# ssslidar_v1_0_blade_PWR_bottom.net
KiCad netlist of a schematic drawn in EAGLE
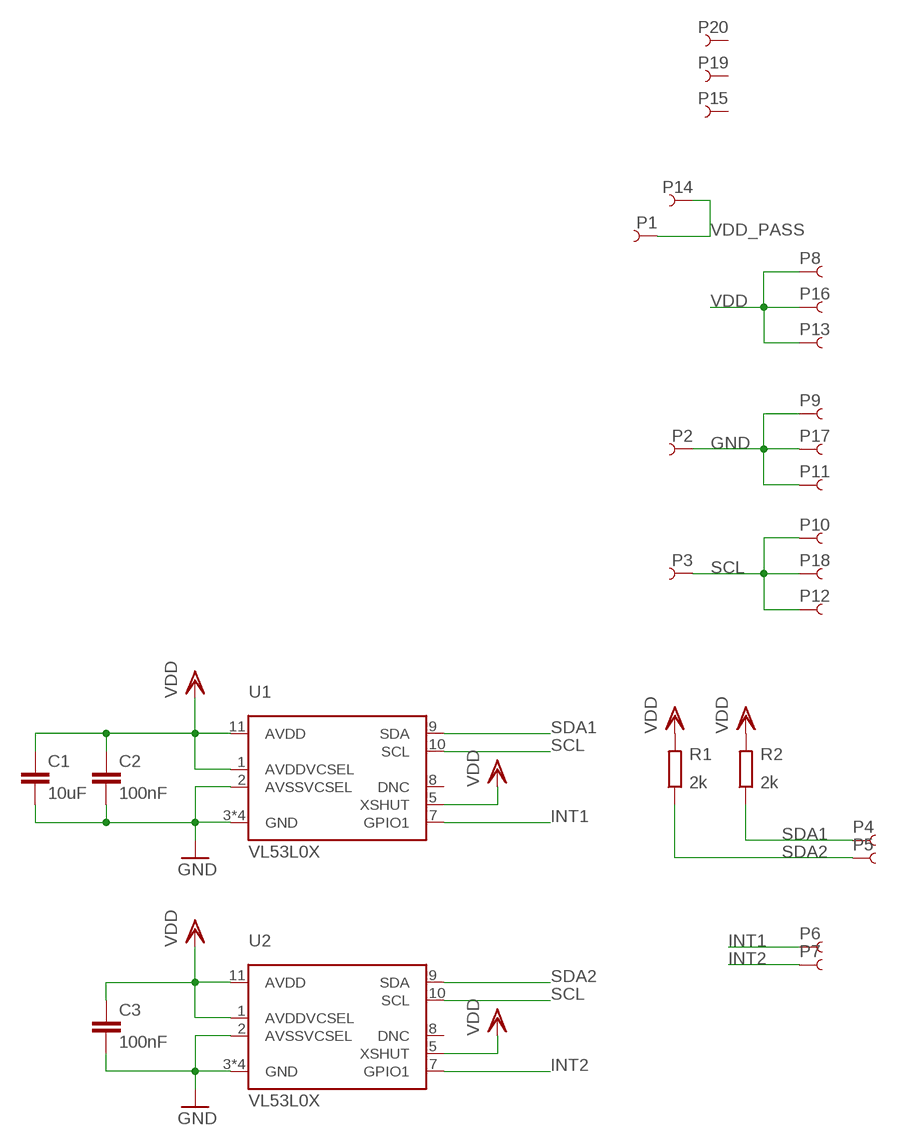
[diagram p0: schematic, sheet 1]

(export (version "E")
  (design (tool "Eeschema 10.0.6"))
  (components
    (comp (ref "C1")
      (value "10uF")
      (footprint "eagle-import:0805_N")
      (libsource (lib "eagle-import") (part "C0805"))
    )
    (comp (ref "C2")
      (value "100nF")
      (footprint "eagle-import:0402_N")
      (libsource (lib "eagle-import") (part "C0402"))
    )
    (comp (ref "C3")
      (value "100nF")
      (footprint "eagle-import:0402_N")
      (libsource (lib "eagle-import") (part "C0402"))
    )
    (comp (ref "P1")
      (value "PIN_SMD_0.8X1_RECT")
      (footprint "eagle-import:PIN_SMD_0.8X1_RECT")
      (libsource (lib "eagle-import") (part "PIN_SMD_0.8X1_RECT"))
    )
    (comp (ref "P2")
      (value "PIN_SMD_1X2")
      (footprint "eagle-import:PIN_SMD_1X2")
      (libsource (lib "eagle-import") (part "PIN_SMD_1X2"))
    )
    (comp (ref "P3")
      (value "PIN_SMD_0.8X1_RECT")
      (footprint "eagle-import:PIN_SMD_0.8X1_RECT")
      (libsource (lib "eagle-import") (part "PIN_SMD_0.8X1_RECT"))
    )
    (comp (ref "P4")
      (value "PIN_SMD_0.8X1_RECT")
      (footprint "eagle-import:PIN_SMD_0.8X1_RECT")
      (libsource (lib "eagle-import") (part "PIN_SMD_0.8X1_RECT"))
    )
    (comp (ref "P5")
      (value "PIN_SMD_0.8X1_RECT")
      (footprint "eagle-import:PIN_SMD_0.8X1_RECT")
      (libsource (lib "eagle-import") (part "PIN_SMD_0.8X1_RECT"))
    )
    (comp (ref "P6")
      (value "PIN_SMD_0.8X1_RECT")
      (footprint "eagle-import:PIN_SMD_0.8X1_RECT")
      (libsource (lib "eagle-import") (part "PIN_SMD_0.8X1_RECT"))
    )
    (comp (ref "P7")
      (value "PIN_SMD_0.8X1_RECT")
      (footprint "eagle-import:PIN_SMD_0.8X1_RECT")
      (libsource (lib "eagle-import") (part "PIN_SMD_0.8X1_RECT"))
    )
    (comp (ref "P8")
      (value "PIN_SMD_0.8X1_RECT")
      (footprint "eagle-import:PIN_SMD_0.8X1_RECT")
      (libsource (lib "eagle-import") (part "PIN_SMD_0.8X1_RECT"))
    )
    (comp (ref "P9")
      (value "PIN_SMD_1X2")
      (footprint "eagle-import:PIN_SMD_1X2")
      (libsource (lib "eagle-import") (part "PIN_SMD_1X2"))
    )
    (comp (ref "P10")
      (value "PIN_SMD_1X2")
      (footprint "eagle-import:PIN_SMD_1X2")
      (libsource (lib "eagle-import") (part "PIN_SMD_1X2"))
    )
    (comp (ref "P11")
      (value "PIN_SMD_1X2")
      (footprint "eagle-import:PIN_SMD_1X2")
      (libsource (lib "eagle-import") (part "PIN_SMD_1X2"))
    )
    (comp (ref "P12")
      (value "PIN_SMD_1X2")
      (footprint "eagle-import:PIN_SMD_1X2")
      (libsource (lib "eagle-import") (part "PIN_SMD_1X2"))
    )
    (comp (ref "P13")
      (value "PIN_SMD_1X2")
      (footprint "eagle-import:PIN_SMD_1X2")
      (libsource (lib "eagle-import") (part "PIN_SMD_1X2"))
    )
    (comp (ref "P14")
      (value "PIN_SMD_0.8X1_RECT")
      (footprint "eagle-import:PIN_SMD_0.8X1_RECT")
      (libsource (lib "eagle-import") (part "PIN_SMD_0.8X1_RECT"))
    )
    (comp (ref "P15")
      (value "PIN_SMD_0.8X1_RECT")
      (footprint "eagle-import:PIN_SMD_0.8X1_RECT")
      (libsource (lib "eagle-import") (part "PIN_SMD_0.8X1_RECT"))
    )
    (comp (ref "P16")
      (value "PIN_SMD_1X2")
      (footprint "eagle-import:PIN_SMD_1X2")
      (libsource (lib "eagle-import") (part "PIN_SMD_1X2"))
    )
    (comp (ref "P17")
      (value "PIN_SMD_1X2")
      (footprint "eagle-import:PIN_SMD_1X2")
      (libsource (lib "eagle-import") (part "PIN_SMD_1X2"))
    )
    (comp (ref "P18")
      (value "PIN_SMD_0.8X1_RECT")
      (footprint "eagle-import:PIN_SMD_0.8X1_RECT")
      (libsource (lib "eagle-import") (part "PIN_SMD_0.8X1_RECT"))
    )
    (comp (ref "P19")
      (value "PIN_SMD_0.8X1_RECT")
      (footprint "eagle-import:PIN_SMD_0.8X1_RECT")
      (libsource (lib "eagle-import") (part "PIN_SMD_0.8X1_RECT"))
    )
    (comp (ref "P20")
      (value "PIN_SMD_0.8X1_RECT")
      (footprint "eagle-import:PIN_SMD_0.8X1_RECT")
      (libsource (lib "eagle-import") (part "PIN_SMD_0.8X1_RECT"))
    )
    (comp (ref "R1")
      (value "2k")
      (footprint "eagle-import:0402_N")
      (libsource (lib "eagle-import") (part "R0402"))
    )
    (comp (ref "R2")
      (value "2k")
      (footprint "eagle-import:0402_N")
      (libsource (lib "eagle-import") (part "R0402"))
    )
    (comp (ref "U1")
      (value "VL53L0X")
      (footprint "eagle-import:VL53L0X")
      (libsource (lib "eagle-import") (part "VL53L0X"))
    )
    (comp (ref "U2")
      (value "VL53L0X")
      (footprint "eagle-import:VL53L0X")
      (libsource (lib "eagle-import") (part "VL53L0X"))
    )
  )
  (nets
    (net (code "1") (name "/INT1") (class "Default")
      (node (ref "P6") (pin "PIN") (pinfunction "1_PIN") (pintype "bidirectional"))
      (node (ref "U1") (pin "7") (pinfunction "GPIO1_7") (pintype "bidirectional"))
    )
    (net (code "2") (name "/INT2") (class "Default")
      (node (ref "P7") (pin "PIN") (pinfunction "1_PIN") (pintype "bidirectional"))
      (node (ref "U2") (pin "7") (pinfunction "GPIO1_7") (pintype "bidirectional"))
    )
    (net (code "3") (name "/SCL") (class "Default")
      (node (ref "P10") (pin "P$1") (pinfunction "1_P$1") (pintype "bidirectional"))
      (node (ref "P12") (pin "P$1") (pinfunction "1_P$1") (pintype "bidirectional"))
      (node (ref "P18") (pin "PIN") (pinfunction "1_PIN") (pintype "bidirectional"))
      (node (ref "P3") (pin "PIN") (pinfunction "1_PIN") (pintype "bidirectional"))
      (node (ref "U1") (pin "10") (pinfunction "SCL_10") (pintype "bidirectional"))
      (node (ref "U2") (pin "10") (pinfunction "SCL_10") (pintype "bidirectional"))
    )
    (net (code "4") (name "/SDA1") (class "Default")
      (node (ref "P4") (pin "PIN") (pinfunction "1_PIN") (pintype "bidirectional"))
      (node (ref "R2") (pin "1") (pinfunction "1_1") (pintype "passive"))
      (node (ref "U1") (pin "9") (pinfunction "SDA_9") (pintype "bidirectional"))
    )
    (net (code "5") (name "/SDA2") (class "Default")
      (node (ref "P5") (pin "PIN") (pinfunction "1_PIN") (pintype "bidirectional"))
      (node (ref "R1") (pin "1") (pinfunction "1_1") (pintype "passive"))
      (node (ref "U2") (pin "9") (pinfunction "SDA_9") (pintype "bidirectional"))
    )
    (net (code "6") (name "/VDD_PASS") (class "Default")
      (node (ref "P1") (pin "PIN") (pinfunction "1_PIN") (pintype "bidirectional"))
      (node (ref "P14") (pin "PIN") (pinfunction "1_PIN") (pintype "bidirectional"))
    )
    (net (code "7") (name "GND") (class "Default")
      (node (ref "C1") (pin "2") (pinfunction "2_2") (pintype "passive"))
      (node (ref "C2") (pin "2") (pinfunction "2_2") (pintype "passive"))
      (node (ref "C3") (pin "2") (pinfunction "2_2") (pintype "passive"))
      (node (ref "P11") (pin "P$1") (pinfunction "1_P$1") (pintype "bidirectional"))
      (node (ref "P17") (pin "P$1") (pinfunction "1_P$1") (pintype "bidirectional"))
      (node (ref "P2") (pin "P$1") (pinfunction "1_P$1") (pintype "bidirectional"))
      (node (ref "P9") (pin "P$1") (pinfunction "1_P$1") (pintype "bidirectional"))
      (node (ref "U1") (pin "12") (pinfunction "GND_12") (pintype "bidirectional"))
      (node (ref "U1") (pin "2") (pinfunction "AVSSVCSEL_2") (pintype "bidirectional"))
      (node (ref "U1") (pin "3") (pinfunction "GND_3") (pintype "bidirectional"))
      (node (ref "U1") (pin "4") (pinfunction "GND_4") (pintype "bidirectional"))
      (node (ref "U1") (pin "6") (pinfunction "GND_6") (pintype "bidirectional"))
      (node (ref "U2") (pin "12") (pinfunction "GND_12") (pintype "bidirectional"))
      (node (ref "U2") (pin "2") (pinfunction "AVSSVCSEL_2") (pintype "bidirectional"))
      (node (ref "U2") (pin "3") (pinfunction "GND_3") (pintype "bidirectional"))
      (node (ref "U2") (pin "4") (pinfunction "GND_4") (pintype "bidirectional"))
      (node (ref "U2") (pin "6") (pinfunction "GND_6") (pintype "bidirectional"))
    )
    (net (code "8") (name "VDD") (class "Default")
      (node (ref "C1") (pin "1") (pinfunction "1_1") (pintype "passive"))
      (node (ref "C2") (pin "1") (pinfunction "1_1") (pintype "passive"))
      (node (ref "C3") (pin "1") (pinfunction "1_1") (pintype "passive"))
      (node (ref "P13") (pin "P$1") (pinfunction "1_P$1") (pintype "bidirectional"))
      (node (ref "P16") (pin "P$1") (pinfunction "1_P$1") (pintype "bidirectional"))
      (node (ref "P8") (pin "PIN") (pinfunction "1_PIN") (pintype "bidirectional"))
      (node (ref "R1") (pin "2") (pinfunction "2_2") (pintype "passive"))
      (node (ref "R2") (pin "2") (pinfunction "2_2") (pintype "passive"))
      (node (ref "U1") (pin "1") (pinfunction "AVDDVCSEL_1") (pintype "bidirectional"))
      (node (ref "U1") (pin "11") (pinfunction "AVDD_11") (pintype "bidirectional"))
      (node (ref "U1") (pin "5") (pinfunction "XSHUT_5") (pintype "bidirectional"))
      (node (ref "U2") (pin "1") (pinfunction "AVDDVCSEL_1") (pintype "bidirectional"))
      (node (ref "U2") (pin "11") (pinfunction "AVDD_11") (pintype "bidirectional"))
      (node (ref "U2") (pin "5") (pinfunction "XSHUT_5") (pintype "bidirectional"))
    )
    (net (code "9") (name "unconnected-(P15-1-PadPIN)") (class "Default")
      (node (ref "P15") (pin "PIN") (pinfunction "1_PIN") (pintype "bidirectional"))
    )
    (net (code "10") (name "unconnected-(P19-1-PadPIN)") (class "Default")
      (node (ref "P19") (pin "PIN") (pinfunction "1_PIN") (pintype "bidirectional"))
    )
    (net (code "11") (name "unconnected-(P20-1-PadPIN)") (class "Default")
      (node (ref "P20") (pin "PIN") (pinfunction "1_PIN") (pintype "bidirectional"))
    )
    (net (code "12") (name "unconnected-(U1-DNC-Pad8)") (class "Default")
      (node (ref "U1") (pin "8") (pinfunction "DNC_8") (pintype "bidirectional"))
    )
    (net (code "13") (name "unconnected-(U2-DNC-Pad8)") (class "Default")
      (node (ref "U2") (pin "8") (pinfunction "DNC_8") (pintype "bidirectional"))
    )
  )
)
